# MotorControllerInterface.net
KiCad netlist of a schematic drawn in Altium Designer
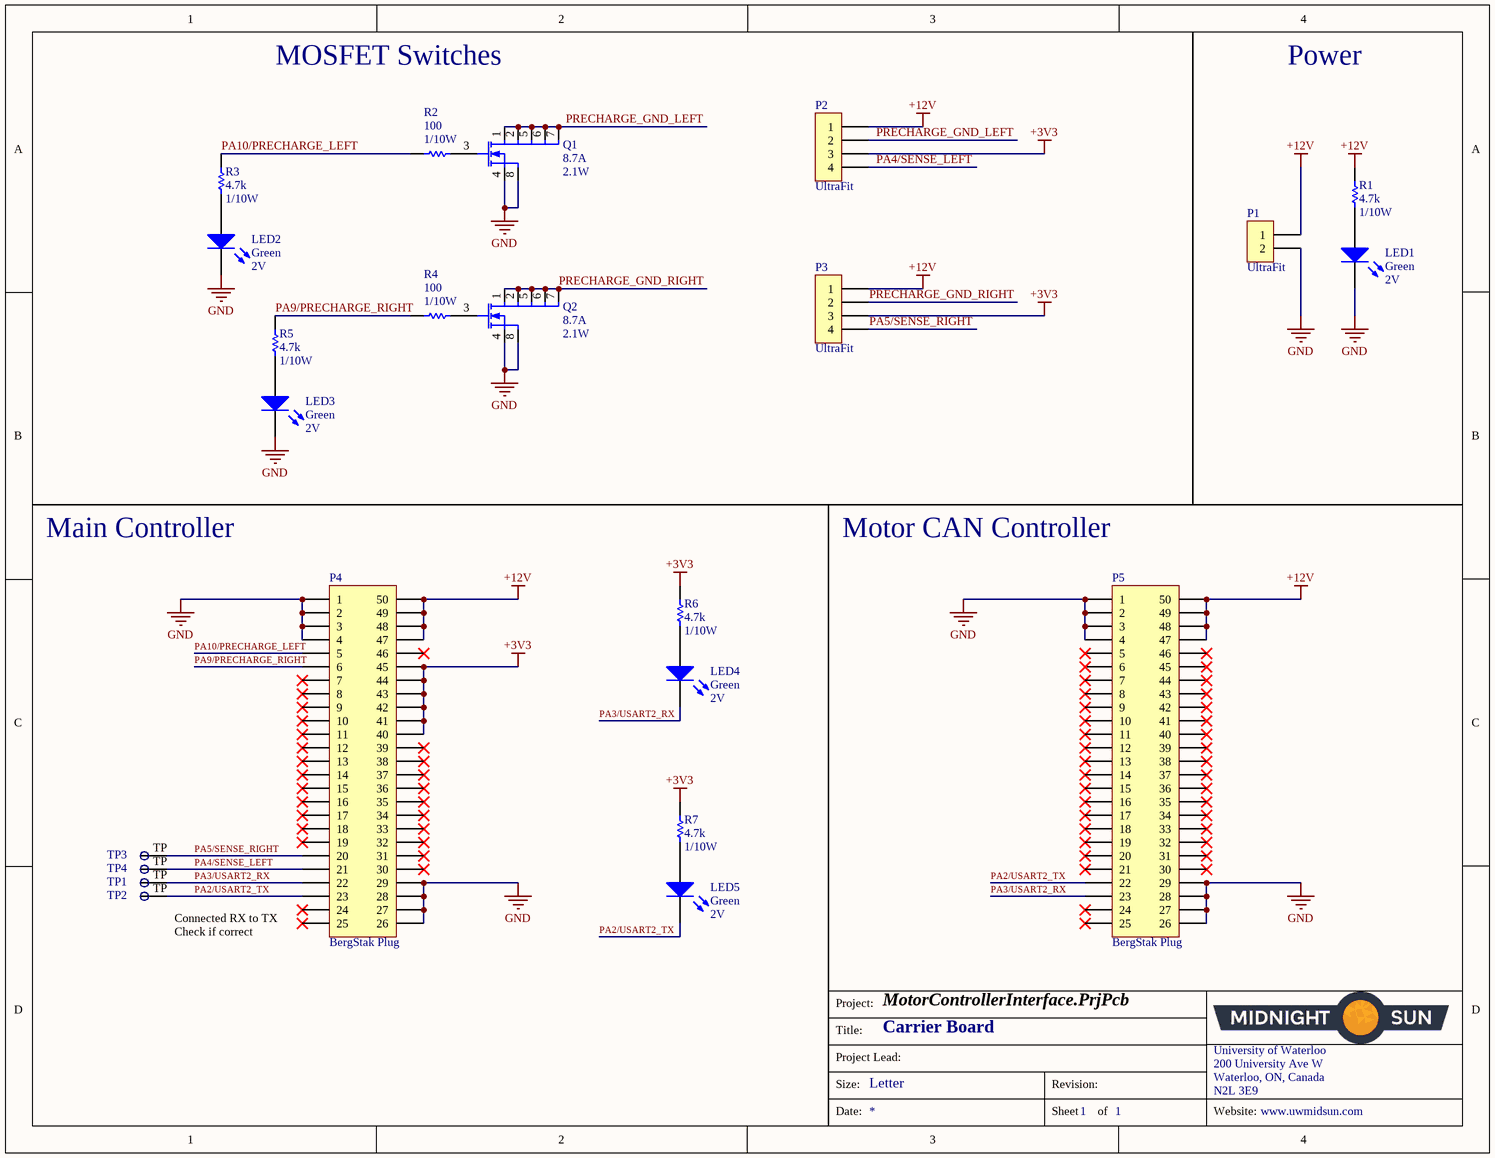
[diagram p0: MotorControllerInterface.SchDoc]

(export (version "E")
  (design (tool "Eeschema 10.0.6"))
  (components
    (comp (ref "LED1")
      (value "LED GREEN CLEAR 2V 0603")
      (footprint "LED_0603")
      (description "Green 572nm LED Indication - Discrete 2V 0603 (1608 Metric)")
      (fields
        (field (name "MANUFACTURER") "Wurth Electronics Inc.")
        (field (name "MANUFACTURER PART NUMBER") "150060VS75000")
        (field (name "COLOR") "Green")
        (field (name "VOLTAGE - FORWARD (VF) (TYP)") "2V")
      )
      (libsource (lib "Schematic Diagrams") (part "LED GREEN CLEAR 2V 0603"))
    )
    (comp (ref "LED2")
      (value "LED GREEN CLEAR 2V 0603")
      (footprint "LED_0603")
      (description "Green 572nm LED Indication - Discrete 2V 0603 (1608 Metric)")
      (fields
        (field (name "MANUFACTURER") "Wurth Electronics Inc.")
        (field (name "MANUFACTURER PART NUMBER") "150060VS75000")
        (field (name "COLOR") "Green")
        (field (name "VOLTAGE - FORWARD (VF) (TYP)") "2V")
      )
      (libsource (lib "Schematic Diagrams") (part "LED GREEN CLEAR 2V 0603"))
    )
    (comp (ref "LED3")
      (value "LED GREEN CLEAR 2V 0603")
      (footprint "LED_0603")
      (description "Green 572nm LED Indication - Discrete 2V 0603 (1608 Metric)")
      (fields
        (field (name "MANUFACTURER") "Wurth Electronics Inc.")
        (field (name "MANUFACTURER PART NUMBER") "150060VS75000")
        (field (name "COLOR") "Green")
        (field (name "VOLTAGE - FORWARD (VF) (TYP)") "2V")
      )
      (libsource (lib "Schematic Diagrams") (part "LED GREEN CLEAR 2V 0603"))
    )
    (comp (ref "LED4")
      (value "LED GREEN CLEAR 2V 0603")
      (footprint "LED_0603")
      (description "Green 572nm LED Indication - Discrete 2V 0603 (1608 Metric)")
      (fields
        (field (name "MANUFACTURER") "Wurth Electronics Inc.")
        (field (name "MANUFACTURER PART NUMBER") "150060VS75000")
        (field (name "COLOR") "Green")
        (field (name "VOLTAGE - FORWARD (VF) (TYP)") "2V")
      )
      (libsource (lib "Schematic Diagrams") (part "LED GREEN CLEAR 2V 0603"))
    )
    (comp (ref "LED5")
      (value "LED GREEN CLEAR 2V 0603")
      (footprint "LED_0603")
      (description "Green 572nm LED Indication - Discrete 2V 0603 (1608 Metric)")
      (fields
        (field (name "MANUFACTURER") "Wurth Electronics Inc.")
        (field (name "MANUFACTURER PART NUMBER") "150060VS75000")
        (field (name "COLOR") "Green")
        (field (name "VOLTAGE - FORWARD (VF) (TYP)") "2V")
      )
      (libsource (lib "Schematic Diagrams") (part "LED GREEN CLEAR 2V 0603"))
    )
    (comp (ref "P1")
      (value "CONN 2POS ULTRA-FIT 0.138\"")
      (footprint "CONN, 2POS ULTRA-FIT")
      (description "2 Positions Header, Shrouded Connector 0.138\" (3.50mm) Through Hole Gold")
      (fields (field (name "VOLTAGE") "400V") (field (name "SERIES") "UltraFit"))
      (libsource (lib "Schematic Diagrams") (part "CONN 2POS ULTRA-FIT 0.138{dblquote}"))
    )
    (comp (ref "P2")
      (value "CONN 4POS ULTRA-FIT 0.138\"")
      (footprint "CONN, 4POS ULTRA-FIT")
      (description "4 Positions Header Connector 0.138\" (3.50mm) Through Hole Tin")
      (fields (field (name "VOLTAGE") "400V") (field (name "SERIES") "UltraFit"))
      (libsource (lib "Schematic Diagrams") (part "CONN 4POS ULTRA-FIT 0.138{dblquote}"))
    )
    (comp (ref "P3")
      (value "CONN 4POS ULTRA-FIT 0.138\"")
      (footprint "CONN, 4POS ULTRA-FIT")
      (description "4 Positions Header Connector 0.138\" (3.50mm) Through Hole Tin")
      (fields (field (name "VOLTAGE") "400V") (field (name "SERIES") "UltraFit"))
      (libsource (lib "Schematic Diagrams") (part "CONN 4POS ULTRA-FIT 0.138{dblquote}"))
    )
    (comp (ref "P4")
      (value "CONN 50POS Bergstak Plug 0.02\"")
      (footprint "CONN, Bergstak 50 Pos Plug")
      (description "50 Position Connector Plug, Outer Shroud Contacts Surface Mount Gold")
      (fields (field (name "SERIES") "BergStak Plug"))
      (libsource (lib "Schematic Diagrams") (part "CONN 50POS Bergstak Plug 0.02{dblquote}"))
    )
    (comp (ref "P5")
      (value "CONN 50POS Bergstak Plug 0.02\"")
      (footprint "CONN, Bergstak 50 Pos Plug")
      (description "50 Position Connector Plug, Outer Shroud Contacts Surface Mount Gold")
      (fields (field (name "SERIES") "BergStak Plug"))
      (libsource (lib "Schematic Diagrams") (part "CONN 50POS Bergstak Plug 0.02{dblquote}"))
    )
    (comp (ref "Q1")
      (value "MOSFET N-CH 30V 8.7A 2.1W 6-PQFN (2x2)")
      (footprint "MOSFET N-CH 30V 12A 2mmx2mm PQFN")
      (fields
        (field (name "CURRENT - CONTINUOUS DRAIN (ID) @ 25°C") "8.7A")
        (field (name "POWER DISSIPATION (MAX)") "2.1W")
      )
      (libsource (lib "Schematic Diagrams") (part "MOSFET N-CH 30V 8.7A 2.1W 6-PQFN (2x2)"))
    )
    (comp (ref "Q2")
      (value "MOSFET N-CH 30V 8.7A 2.1W 6-PQFN (2x2)")
      (footprint "MOSFET N-CH 30V 12A 2mmx2mm PQFN")
      (fields
        (field (name "CURRENT - CONTINUOUS DRAIN (ID) @ 25°C") "8.7A")
        (field (name "POWER DISSIPATION (MAX)") "2.1W")
      )
      (libsource (lib "Schematic Diagrams") (part "MOSFET N-CH 30V 8.7A 2.1W 6-PQFN (2x2)"))
    )
    (comp (ref "R1")
      (value "RES 4.7K OHM 1% 1/10W 0603")
      (footprint "RES, 0603")
      (description "4.7k Ohm ±1% 0.1W, 1/10W Chip Resistor 0603 (1608 Metric) Moisture Resistant Thick Film")
      (fields
        (field (name "TOLERANCE") "±1%")
        (field (name "RESISTANCE (OHMS)") "4.7k")
        (field (name "POWER (WATTS)") "1/10W")
      )
      (libsource (lib "Schematic Diagrams") (part "RES 4.7K OHM 1% 1/10W 0603"))
    )
    (comp (ref "R2")
      (value "RES 100 OHM 1% 1/10W 0603")
      (footprint "RES, 0603")
      (description "100 Ohm ±1% 0.1W, 1/10W Chip Resistor 0603 (1608 Metric) Moisture Resistant Thick Film")
      (fields
        (field (name "TOLERANCE") "±1%")
        (field (name "RESISTANCE") "100")
        (field (name "POWER") "1/10W")
      )
      (libsource (lib "Schematic Diagrams") (part "RES 100 OHM 1% 1/10W 0603"))
    )
    (comp (ref "R3")
      (value "RES 4.7K OHM 1% 1/10W 0603")
      (footprint "RES, 0603")
      (description "4.7k Ohm ±1% 0.1W, 1/10W Chip Resistor 0603 (1608 Metric) Moisture Resistant Thick Film")
      (fields
        (field (name "TOLERANCE") "±1%")
        (field (name "RESISTANCE (OHMS)") "4.7k")
        (field (name "POWER (WATTS)") "1/10W")
      )
      (libsource (lib "Schematic Diagrams") (part "RES 4.7K OHM 1% 1/10W 0603"))
    )
    (comp (ref "R4")
      (value "RES 100 OHM 1% 1/10W 0603")
      (footprint "RES, 0603")
      (description "100 Ohm ±1% 0.1W, 1/10W Chip Resistor 0603 (1608 Metric) Moisture Resistant Thick Film")
      (fields
        (field (name "TOLERANCE") "±1%")
        (field (name "RESISTANCE") "100")
        (field (name "POWER") "1/10W")
      )
      (libsource (lib "Schematic Diagrams") (part "RES 100 OHM 1% 1/10W 0603"))
    )
    (comp (ref "R5")
      (value "RES 4.7K OHM 1% 1/10W 0603")
      (footprint "RES, 0603")
      (description "4.7k Ohm ±1% 0.1W, 1/10W Chip Resistor 0603 (1608 Metric) Moisture Resistant Thick Film")
      (fields
        (field (name "TOLERANCE") "±1%")
        (field (name "RESISTANCE (OHMS)") "4.7k")
        (field (name "POWER (WATTS)") "1/10W")
      )
      (libsource (lib "Schematic Diagrams") (part "RES 4.7K OHM 1% 1/10W 0603"))
    )
    (comp (ref "R6")
      (value "RES 4.7K OHM 1% 1/10W 0603")
      (footprint "RES, 0603")
      (description "4.7k Ohm ±1% 0.1W, 1/10W Chip Resistor 0603 (1608 Metric) Moisture Resistant Thick Film")
      (fields
        (field (name "TOLERANCE") "±1%")
        (field (name "RESISTANCE (OHMS)") "4.7k")
        (field (name "POWER (WATTS)") "1/10W")
      )
      (libsource (lib "Schematic Diagrams") (part "RES 4.7K OHM 1% 1/10W 0603"))
    )
    (comp (ref "R7")
      (value "RES 4.7K OHM 1% 1/10W 0603")
      (footprint "RES, 0603")
      (description "4.7k Ohm ±1% 0.1W, 1/10W Chip Resistor 0603 (1608 Metric) Moisture Resistant Thick Film")
      (fields
        (field (name "TOLERANCE") "±1%")
        (field (name "RESISTANCE (OHMS)") "4.7k")
        (field (name "POWER (WATTS)") "1/10W")
      )
      (libsource (lib "Schematic Diagrams") (part "RES 4.7K OHM 1% 1/10W 0603"))
    )
    (comp (ref "TP1")
      (value "USART2_RX")
      (footprint "Test Point")
      (libsource (lib "Schematic Diagrams") (part "Test Point"))
    )
    (comp (ref "TP2")
      (value "USART2_TX")
      (footprint "Test Point")
      (libsource (lib "Schematic Diagrams") (part "Test Point"))
    )
    (comp (ref "TP3")
      (value "SENSE_RIGHT")
      (footprint "Test Point")
      (libsource (lib "Schematic Diagrams") (part "Test Point"))
    )
    (comp (ref "TP4")
      (value "SENSE_LEFT")
      (footprint "Test Point")
      (libsource (lib "Schematic Diagrams") (part "Test Point"))
    )
  )
  (nets
    (net (code "1") (name "+3V3") (class "Default")
      (node (ref "P2") (pin "3") (pinfunction "3_3") (pintype "passive"))
      (node (ref "P3") (pin "3") (pinfunction "3_3") (pintype "passive"))
      (node (ref "P4") (pin "40") (pinfunction "40_40") (pintype "passive"))
      (node (ref "P4") (pin "41") (pinfunction "41_41") (pintype "passive"))
      (node (ref "P4") (pin "42") (pinfunction "42_42") (pintype "passive"))
      (node (ref "P4") (pin "43") (pinfunction "43_43") (pintype "passive"))
      (node (ref "P4") (pin "44") (pinfunction "44_44") (pintype "passive"))
      (node (ref "P4") (pin "45") (pinfunction "45_45") (pintype "passive"))
      (node (ref "R6") (pin "1") (pinfunction "1_1") (pintype "passive"))
      (node (ref "R7") (pin "1") (pinfunction "1_1") (pintype "passive"))
    )
    (net (code "2") (name "+12V") (class "Default")
      (node (ref "P1") (pin "1") (pinfunction "1_1") (pintype "passive"))
      (node (ref "P2") (pin "1") (pinfunction "1_1") (pintype "passive"))
      (node (ref "P3") (pin "1") (pinfunction "1_1") (pintype "passive"))
      (node (ref "P4") (pin "47") (pinfunction "47_47") (pintype "passive"))
      (node (ref "P4") (pin "48") (pinfunction "48_48") (pintype "passive"))
      (node (ref "P4") (pin "49") (pinfunction "49_49") (pintype "passive"))
      (node (ref "P4") (pin "50") (pinfunction "50_50") (pintype "passive"))
      (node (ref "P5") (pin "47") (pinfunction "47_47") (pintype "passive"))
      (node (ref "P5") (pin "48") (pinfunction "48_48") (pintype "passive"))
      (node (ref "P5") (pin "49") (pinfunction "49_49") (pintype "passive"))
      (node (ref "P5") (pin "50") (pinfunction "50_50") (pintype "passive"))
      (node (ref "R1") (pin "1") (pinfunction "1_1") (pintype "passive"))
    )
    (net (code "3") (name "/PA2{slash}USART2_TX") (class "Default")
      (node (ref "LED5") (pin "2") (pinfunction "K_2") (pintype "passive"))
      (node (ref "P4") (pin "23") (pinfunction "23_23") (pintype "passive"))
      (node (ref "P5") (pin "22") (pinfunction "22_22") (pintype "passive"))
      (node (ref "TP2") (pin "TP") (pinfunction "1_TP") (pintype "passive"))
    )
    (net (code "4") (name "/PA3{slash}USART2_RX") (class "Default")
      (node (ref "LED4") (pin "2") (pinfunction "K_2") (pintype "passive"))
      (node (ref "P4") (pin "22") (pinfunction "22_22") (pintype "passive"))
      (node (ref "P5") (pin "23") (pinfunction "23_23") (pintype "passive"))
      (node (ref "TP1") (pin "TP") (pinfunction "1_TP") (pintype "passive"))
    )
    (net (code "5") (name "/PA4{slash}SENSE_LEFT") (class "Default")
      (node (ref "P2") (pin "4") (pinfunction "4_4") (pintype "passive"))
      (node (ref "P4") (pin "21") (pinfunction "21_21") (pintype "passive"))
      (node (ref "TP4") (pin "TP") (pinfunction "1_TP") (pintype "passive"))
    )
    (net (code "6") (name "/PA5{slash}SENSE_RIGHT") (class "Default")
      (node (ref "P3") (pin "4") (pinfunction "4_4") (pintype "passive"))
      (node (ref "P4") (pin "20") (pinfunction "20_20") (pintype "passive"))
      (node (ref "TP3") (pin "TP") (pinfunction "1_TP") (pintype "passive"))
    )
    (net (code "7") (name "/PA9{slash}PRECHARGE_RIGHT") (class "Default")
      (node (ref "P4") (pin "6") (pinfunction "6_6") (pintype "passive"))
      (node (ref "R4") (pin "1") (pinfunction "1_1") (pintype "passive"))
      (node (ref "R5") (pin "1") (pinfunction "1_1") (pintype "passive"))
    )
    (net (code "8") (name "/PA10{slash}PRECHARGE_LEFT") (class "Default")
      (node (ref "P4") (pin "5") (pinfunction "5_5") (pintype "passive"))
      (node (ref "R2") (pin "1") (pinfunction "1_1") (pintype "passive"))
      (node (ref "R3") (pin "1") (pinfunction "1_1") (pintype "passive"))
    )
    (net (code "9") (name "/PRECHARGE_GND_LEFT") (class "Default")
      (node (ref "P2") (pin "2") (pinfunction "2_2") (pintype "passive"))
      (node (ref "Q1") (pin "1") (pinfunction "D_1") (pintype "passive"))
      (node (ref "Q1") (pin "2") (pinfunction "D_2") (pintype "passive"))
      (node (ref "Q1") (pin "5") (pinfunction "D_5") (pintype "passive"))
      (node (ref "Q1") (pin "6") (pinfunction "D_6") (pintype "passive"))
      (node (ref "Q1") (pin "7") (pinfunction "D_7") (pintype "passive"))
    )
    (net (code "10") (name "/PRECHARGE_GND_RIGHT") (class "Default")
      (node (ref "P3") (pin "2") (pinfunction "2_2") (pintype "passive"))
      (node (ref "Q2") (pin "1") (pinfunction "D_1") (pintype "passive"))
      (node (ref "Q2") (pin "2") (pinfunction "D_2") (pintype "passive"))
      (node (ref "Q2") (pin "5") (pinfunction "D_5") (pintype "passive"))
      (node (ref "Q2") (pin "6") (pinfunction "D_6") (pintype "passive"))
      (node (ref "Q2") (pin "7") (pinfunction "D_7") (pintype "passive"))
    )
    (net (code "11") (name "GND") (class "Default")
      (node (ref "LED1") (pin "2") (pinfunction "K_2") (pintype "passive"))
      (node (ref "LED2") (pin "2") (pinfunction "K_2") (pintype "passive"))
      (node (ref "LED3") (pin "2") (pinfunction "K_2") (pintype "passive"))
      (node (ref "P1") (pin "2") (pinfunction "2_2") (pintype "passive"))
      (node (ref "P4") (pin "1") (pinfunction "1_1") (pintype "passive"))
      (node (ref "P4") (pin "2") (pinfunction "2_2") (pintype "passive"))
      (node (ref "P4") (pin "26") (pinfunction "26_26") (pintype "passive"))
      (node (ref "P4") (pin "27") (pinfunction "27_27") (pintype "passive"))
      (node (ref "P4") (pin "28") (pinfunction "28_28") (pintype "passive"))
      (node (ref "P4") (pin "29") (pinfunction "29_29") (pintype "passive"))
      (node (ref "P4") (pin "3") (pinfunction "3_3") (pintype "passive"))
      (node (ref "P4") (pin "4") (pinfunction "4_4") (pintype "passive"))
      (node (ref "P5") (pin "1") (pinfunction "1_1") (pintype "passive"))
      (node (ref "P5") (pin "2") (pinfunction "2_2") (pintype "passive"))
      (node (ref "P5") (pin "26") (pinfunction "26_26") (pintype "passive"))
      (node (ref "P5") (pin "27") (pinfunction "27_27") (pintype "passive"))
      (node (ref "P5") (pin "28") (pinfunction "28_28") (pintype "passive"))
      (node (ref "P5") (pin "29") (pinfunction "29_29") (pintype "passive"))
      (node (ref "P5") (pin "3") (pinfunction "3_3") (pintype "passive"))
      (node (ref "P5") (pin "4") (pinfunction "4_4") (pintype "passive"))
      (node (ref "Q1") (pin "4") (pinfunction "S_4") (pintype "passive"))
      (node (ref "Q1") (pin "8") (pinfunction "S_8") (pintype "passive"))
      (node (ref "Q2") (pin "4") (pinfunction "S_4") (pintype "passive"))
      (node (ref "Q2") (pin "8") (pinfunction "S_8") (pintype "passive"))
    )
    (net (code "12") (name "Net-(LED1-A)") (class "Default")
      (node (ref "LED1") (pin "1") (pinfunction "A_1") (pintype "passive"))
      (node (ref "R1") (pin "2") (pinfunction "2_2") (pintype "passive"))
    )
    (net (code "13") (name "Net-(LED2-A)") (class "Default")
      (node (ref "LED2") (pin "1") (pinfunction "A_1") (pintype "passive"))
      (node (ref "R3") (pin "2") (pinfunction "2_2") (pintype "passive"))
    )
    (net (code "14") (name "Net-(LED3-A)") (class "Default")
      (node (ref "LED3") (pin "1") (pinfunction "A_1") (pintype "passive"))
      (node (ref "R5") (pin "2") (pinfunction "2_2") (pintype "passive"))
    )
    (net (code "15") (name "Net-(LED4-A)") (class "Default")
      (node (ref "LED4") (pin "1") (pinfunction "A_1") (pintype "passive"))
      (node (ref "R6") (pin "2") (pinfunction "2_2") (pintype "passive"))
    )
    (net (code "16") (name "Net-(LED5-A)") (class "Default")
      (node (ref "LED5") (pin "1") (pinfunction "A_1") (pintype "passive"))
      (node (ref "R7") (pin "2") (pinfunction "2_2") (pintype "passive"))
    )
    (net (code "17") (name "Net-(Q1-G)") (class "Default")
      (node (ref "Q1") (pin "3") (pinfunction "G_3") (pintype "passive"))
      (node (ref "R2") (pin "2") (pinfunction "2_2") (pintype "passive"))
    )
    (net (code "18") (name "Net-(Q2-G)") (class "Default")
      (node (ref "Q2") (pin "3") (pinfunction "G_3") (pintype "passive"))
      (node (ref "R4") (pin "2") (pinfunction "2_2") (pintype "passive"))
    )
    (net (code "19") (name "unconnected-(P4-Pad7)") (class "Default")
      (node (ref "P4") (pin "7") (pinfunction "7_7") (pintype "passive+no_connect"))
    )
    (net (code "20") (name "unconnected-(P4-Pad8)") (class "Default")
      (node (ref "P4") (pin "8") (pinfunction "8_8") (pintype "passive+no_connect"))
    )
    (net (code "21") (name "unconnected-(P4-Pad9)") (class "Default")
      (node (ref "P4") (pin "9") (pinfunction "9_9") (pintype "passive+no_connect"))
    )
    (net (code "22") (name "unconnected-(P4-Pad10)") (class "Default")
      (node (ref "P4") (pin "10") (pinfunction "10_10") (pintype "passive+no_connect"))
    )
    (net (code "23") (name "unconnected-(P4-Pad11)") (class "Default")
      (node (ref "P4") (pin "11") (pinfunction "11_11") (pintype "passive+no_connect"))
    )
    (net (code "24") (name "unconnected-(P4-Pad12)") (class "Default")
      (node (ref "P4") (pin "12") (pinfunction "12_12") (pintype "passive+no_connect"))
    )
    (net (code "25") (name "unconnected-(P4-Pad13)") (class "Default")
      (node (ref "P4") (pin "13") (pinfunction "13_13") (pintype "passive+no_connect"))
    )
    (net (code "26") (name "unconnected-(P4-Pad14)") (class "Default")
      (node (ref "P4") (pin "14") (pinfunction "14_14") (pintype "passive+no_connect"))
    )
    (net (code "27") (name "unconnected-(P4-Pad15)") (class "Default")
      (node (ref "P4") (pin "15") (pinfunction "15_15") (pintype "passive+no_connect"))
    )
    (net (code "28") (name "unconnected-(P4-Pad16)") (class "Default")
      (node (ref "P4") (pin "16") (pinfunction "16_16") (pintype "passive+no_connect"))
    )
    (net (code "29") (name "unconnected-(P4-Pad17)") (class "Default")
      (node (ref "P4") (pin "17") (pinfunction "17_17") (pintype "passive+no_connect"))
    )
    (net (code "30") (name "unconnected-(P4-Pad18)") (class "Default")
      (node (ref "P4") (pin "18") (pinfunction "18_18") (pintype "passive+no_connect"))
    )
    (net (code "31") (name "unconnected-(P4-Pad19)") (class "Default")
      (node (ref "P4") (pin "19") (pinfunction "19_19") (pintype "passive+no_connect"))
    )
    (net (code "32") (name "unconnected-(P4-Pad24)") (class "Default")
      (node (ref "P4") (pin "24") (pinfunction "24_24") (pintype "passive+no_connect"))
    )
    (net (code "33") (name "unconnected-(P4-Pad25)") (class "Default")
      (node (ref "P4") (pin "25") (pinfunction "25_25") (pintype "passive+no_connect"))
    )
    (net (code "34") (name "unconnected-(P4-Pad30)") (class "Default")
      (node (ref "P4") (pin "30") (pinfunction "30_30") (pintype "passive+no_connect"))
    )
    (net (code "35") (name "unconnected-(P4-Pad31)") (class "Default")
      (node (ref "P4") (pin "31") (pinfunction "31_31") (pintype "passive+no_connect"))
    )
    (net (code "36") (name "unconnected-(P4-Pad32)") (class "Default")
      (node (ref "P4") (pin "32") (pinfunction "32_32") (pintype "passive+no_connect"))
    )
    (net (code "37") (name "unconnected-(P4-Pad33)") (class "Default")
      (node (ref "P4") (pin "33") (pinfunction "33_33") (pintype "passive+no_connect"))
    )
    (net (code "38") (name "unconnected-(P4-Pad34)") (class "Default")
      (node (ref "P4") (pin "34") (pinfunction "34_34") (pintype "passive+no_connect"))
    )
    (net (code "39") (name "unconnected-(P4-Pad35)") (class "Default")
      (node (ref "P4") (pin "35") (pinfunction "35_35") (pintype "passive+no_connect"))
    )
    (net (code "40") (name "unconnected-(P4-Pad36)") (class "Default")
      (node (ref "P4") (pin "36") (pinfunction "36_36") (pintype "passive+no_connect"))
    )
    (net (code "41") (name "unconnected-(P4-Pad37)") (class "Default")
      (node (ref "P4") (pin "37") (pinfunction "37_37") (pintype "passive+no_connect"))
    )
    (net (code "42") (name "unconnected-(P4-Pad38)") (class "Default")
      (node (ref "P4") (pin "38") (pinfunction "38_38") (pintype "passive+no_connect"))
    )
    (net (code "43") (name "unconnected-(P4-Pad39)") (class "Default")
      (node (ref "P4") (pin "39") (pinfunction "39_39") (pintype "passive+no_connect"))
    )
    (net (code "44") (name "unconnected-(P4-Pad46)") (class "Default")
      (node (ref "P4") (pin "46") (pinfunction "46_46") (pintype "passive+no_connect"))
    )
    (net (code "45") (name "unconnected-(P5-Pad5)") (class "Default")
      (node (ref "P5") (pin "5") (pinfunction "5_5") (pintype "passive+no_connect"))
    )
    (net (code "46") (name "unconnected-(P5-Pad6)") (class "Default")
      (node (ref "P5") (pin "6") (pinfunction "6_6") (pintype "passive+no_connect"))
    )
    (net (code "47") (name "unconnected-(P5-Pad7)") (class "Default")
      (node (ref "P5") (pin "7") (pinfunction "7_7") (pintype "passive+no_connect"))
    )
    (net (code "48") (name "unconnected-(P5-Pad8)") (class "Default")
      (node (ref "P5") (pin "8") (pinfunction "8_8") (pintype "passive+no_connect"))
    )
    (net (code "49") (name "unconnected-(P5-Pad9)") (class "Default")
      (node (ref "P5") (pin "9") (pinfunction "9_9") (pintype "passive+no_connect"))
    )
    (net (code "50") (name "unconnected-(P5-Pad10)") (class "Default")
      (node (ref "P5") (pin "10") (pinfunction "10_10") (pintype "passive+no_connect"))
    )
    (net (code "51") (name "unconnected-(P5-Pad11)") (class "Default")
      (node (ref "P5") (pin "11") (pinfunction "11_11") (pintype "passive+no_connect"))
    )
    (net (code "52") (name "unconnected-(P5-Pad12)") (class "Default")
      (node (ref "P5") (pin "12") (pinfunction "12_12") (pintype "passive+no_connect"))
    )
    (net (code "53") (name "unconnected-(P5-Pad13)") (class "Default")
      (node (ref "P5") (pin "13") (pinfunction "13_13") (pintype "passive+no_connect"))
    )
    (net (code "54") (name "unconnected-(P5-Pad14)") (class "Default")
      (node (ref "P5") (pin "14") (pinfunction "14_14") (pintype "passive+no_connect"))
    )
    (net (code "55") (name "unconnected-(P5-Pad15)") (class "Default")
      (node (ref "P5") (pin "15") (pinfunction "15_15") (pintype "passive+no_connect"))
    )
    (net (code "56") (name "unconnected-(P5-Pad16)") (class "Default")
      (node (ref "P5") (pin "16") (pinfunction "16_16") (pintype "passive+no_connect"))
    )
    (net (code "57") (name "unconnected-(P5-Pad17)") (class "Default")
      (node (ref "P5") (pin "17") (pinfunction "17_17") (pintype "passive+no_connect"))
    )
    (net (code "58") (name "unconnected-(P5-Pad18)") (class "Default")
      (node (ref "P5") (pin "18") (pinfunction "18_18") (pintype "passive+no_connect"))
    )
    (net (code "59") (name "unconnected-(P5-Pad19)") (class "Default")
      (node (ref "P5") (pin "19") (pinfunction "19_19") (pintype "passive+no_connect"))
    )
    (net (code "60") (name "unconnected-(P5-Pad20)") (class "Default")
      (node (ref "P5") (pin "20") (pinfunction "20_20") (pintype "passive+no_connect"))
    )
    (net (code "61") (name "unconnected-(P5-Pad21)") (class "Default")
      (node (ref "P5") (pin "21") (pinfunction "21_21") (pintype "passive+no_connect"))
    )
    (net (code "62") (name "unconnected-(P5-Pad24)") (class "Default")
      (node (ref "P5") (pin "24") (pinfunction "24_24") (pintype "passive+no_connect"))
    )
    (net (code "63") (name "unconnected-(P5-Pad25)") (class "Default")
      (node (ref "P5") (pin "25") (pinfunction "25_25") (pintype "passive+no_connect"))
    )
    (net (code "64") (name "unconnected-(P5-Pad30)") (class "Default")
      (node (ref "P5") (pin "30") (pinfunction "30_30") (pintype "passive+no_connect"))
    )
    (net (code "65") (name "unconnected-(P5-Pad31)") (class "Default")
      (node (ref "P5") (pin "31") (pinfunction "31_31") (pintype "passive+no_connect"))
    )
    (net (code "66") (name "unconnected-(P5-Pad32)") (class "Default")
      (node (ref "P5") (pin "32") (pinfunction "32_32") (pintype "passive+no_connect"))
    )
    (net (code "67") (name "unconnected-(P5-Pad33)") (class "Default")
      (node (ref "P5") (pin "33") (pinfunction "33_33") (pintype "passive+no_connect"))
    )
    (net (code "68") (name "unconnected-(P5-Pad34)") (class "Default")
      (node (ref "P5") (pin "34") (pinfunction "34_34") (pintype "passive+no_connect"))
    )
    (net (code "69") (name "unconnected-(P5-Pad35)") (class "Default")
      (node (ref "P5") (pin "35") (pinfunction "35_35") (pintype "passive+no_connect"))
    )
    (net (code "70") (name "unconnected-(P5-Pad36)") (class "Default")
      (node (ref "P5") (pin "36") (pinfunction "36_36") (pintype "passive+no_connect"))
    )
    (net (code "71") (name "unconnected-(P5-Pad37)") (class "Default")
      (node (ref "P5") (pin "37") (pinfunction "37_37") (pintype "passive+no_connect"))
    )
    (net (code "72") (name "unconnected-(P5-Pad38)") (class "Default")
      (node (ref "P5") (pin "38") (pinfunction "38_38") (pintype "passive+no_connect"))
    )
    (net (code "73") (name "unconnected-(P5-Pad39)") (class "Default")
      (node (ref "P5") (pin "39") (pinfunction "39_39") (pintype "passive+no_connect"))
    )
    (net (code "74") (name "unconnected-(P5-Pad40)") (class "Default")
      (node (ref "P5") (pin "40") (pinfunction "40_40") (pintype "passive+no_connect"))
    )
    (net (code "75") (name "unconnected-(P5-Pad41)") (class "Default")
      (node (ref "P5") (pin "41") (pinfunction "41_41") (pintype "passive+no_connect"))
    )
    (net (code "76") (name "unconnected-(P5-Pad42)") (class "Default")
      (node (ref "P5") (pin "42") (pinfunction "42_42") (pintype "passive+no_connect"))
    )
    (net (code "77") (name "unconnected-(P5-Pad43)") (class "Default")
      (node (ref "P5") (pin "43") (pinfunction "43_43") (pintype "passive+no_connect"))
    )
    (net (code "78") (name "unconnected-(P5-Pad44)") (class "Default")
      (node (ref "P5") (pin "44") (pinfunction "44_44") (pintype "passive+no_connect"))
    )
    (net (code "79") (name "unconnected-(P5-Pad45)") (class "Default")
      (node (ref "P5") (pin "45") (pinfunction "45_45") (pintype "passive+no_connect"))
    )
    (net (code "80") (name "unconnected-(P5-Pad46)") (class "Default")
      (node (ref "P5") (pin "46") (pinfunction "46_46") (pintype "passive+no_connect"))
    )
  )
)
